# Msi2500.net
KiCad netlist of a schematic drawn in Altium Designer
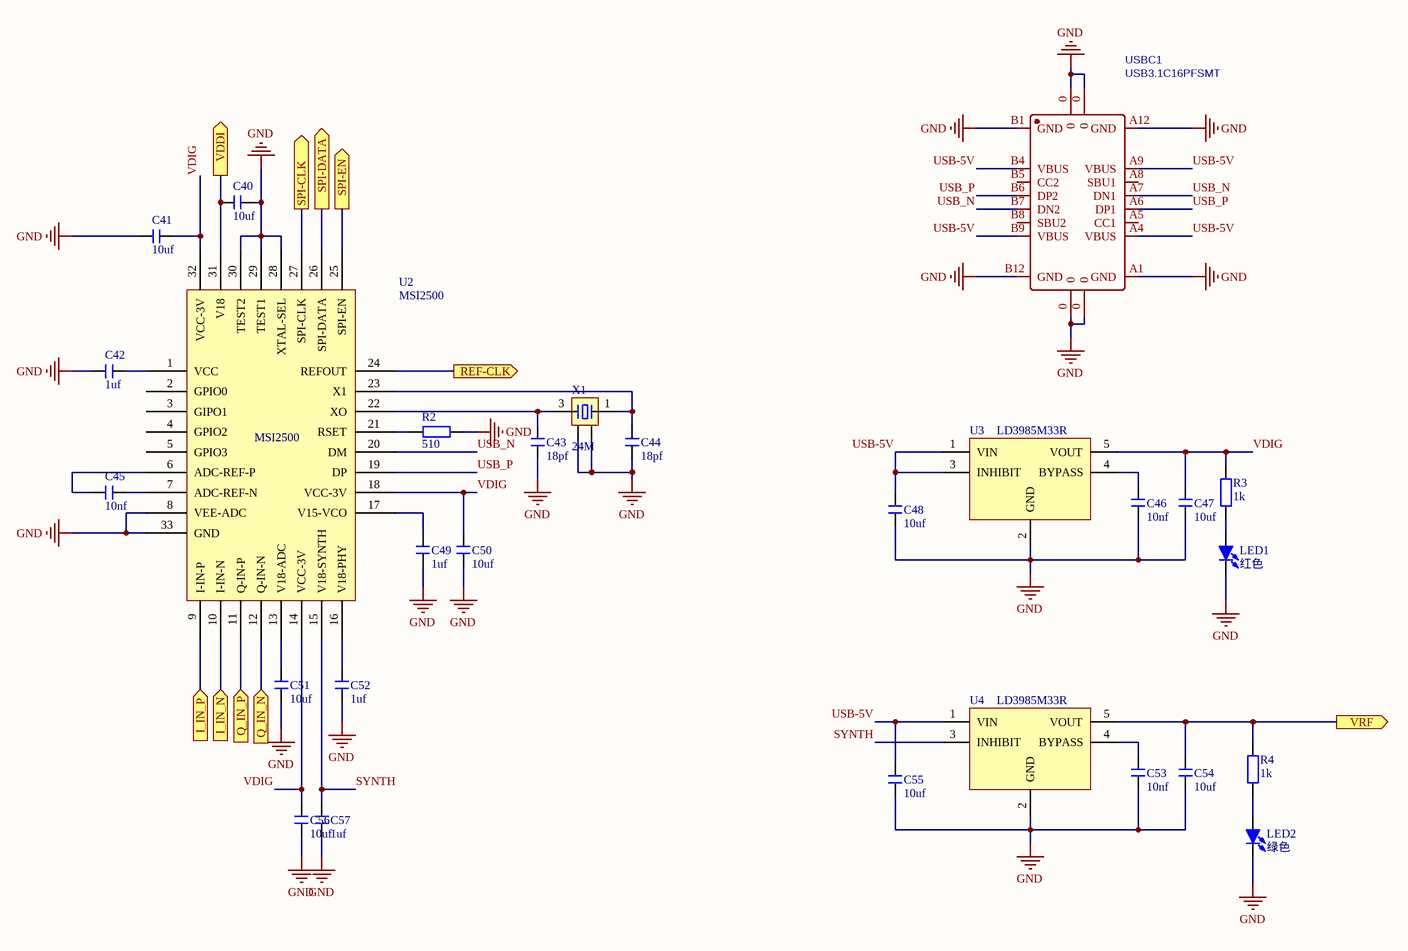
[diagram p0: Msi2500.SchDoc]

(export (version "E")
  (design (tool "Eeschema 10.0.6"))
  (components
    (comp (ref "C40")
      (value "10uf")
      (footprint "C 0603_M")
      (description "无极性贴片电容")
      (fields (field (name "版权归属") "源创客"))
      (libsource (lib "电阻-电容-电感") (part "C"))
    )
    (comp (ref "C41")
      (value "10uf")
      (footprint "C 0603_M")
      (description "无极性贴片电容")
      (fields (field (name "版权归属") "源创客"))
      (libsource (lib "电阻-电容-电感") (part "C"))
    )
    (comp (ref "C42")
      (value "1uf")
      (footprint "C 0603_M")
      (description "无极性贴片电容")
      (fields (field (name "版权归属") "源创客"))
      (libsource (lib "电阻-电容-电感") (part "C"))
    )
    (comp (ref "C43")
      (value "18pf")
      (footprint "C 0603_M")
      (description "无极性贴片电容")
      (fields (field (name "版权归属") "源创客"))
      (libsource (lib "电阻-电容-电感") (part "C"))
    )
    (comp (ref "C44")
      (value "18pf")
      (footprint "C 0603_M")
      (description "无极性贴片电容")
      (fields (field (name "版权归属") "源创客"))
      (libsource (lib "电阻-电容-电感") (part "C"))
    )
    (comp (ref "C45")
      (value "10nf")
      (footprint "C 0603_M")
      (description "无极性贴片电容")
      (fields (field (name "版权归属") "源创客"))
      (libsource (lib "电阻-电容-电感") (part "C"))
    )
    (comp (ref "C46")
      (value "10nf")
      (footprint "C 0603_M")
      (description "无极性贴片电容")
      (fields (field (name "版权归属") "源创客"))
      (libsource (lib "电阻-电容-电感") (part "C"))
    )
    (comp (ref "C47")
      (value "10uf")
      (footprint "C 0603_M")
      (description "无极性贴片电容")
      (fields (field (name "版权归属") "源创客"))
      (libsource (lib "电阻-电容-电感") (part "C"))
    )
    (comp (ref "C48")
      (value "10uf")
      (footprint "C 0603_M")
      (description "无极性贴片电容")
      (fields (field (name "版权归属") "源创客"))
      (libsource (lib "电阻-电容-电感") (part "C"))
    )
    (comp (ref "C49")
      (value "1uf")
      (footprint "C 0603_M")
      (description "无极性贴片电容")
      (fields (field (name "版权归属") "源创客"))
      (libsource (lib "电阻-电容-电感") (part "C"))
    )
    (comp (ref "C50")
      (value "10uf")
      (footprint "C 0603_M")
      (description "无极性贴片电容")
      (fields (field (name "版权归属") "源创客"))
      (libsource (lib "电阻-电容-电感") (part "C"))
    )
    (comp (ref "C51")
      (value "10uf")
      (footprint "C 0603_M")
      (description "无极性贴片电容")
      (fields (field (name "版权归属") "源创客"))
      (libsource (lib "电阻-电容-电感") (part "C"))
    )
    (comp (ref "C52")
      (value "1uf")
      (footprint "C 0603_M")
      (description "无极性贴片电容")
      (fields (field (name "版权归属") "源创客"))
      (libsource (lib "电阻-电容-电感") (part "C"))
    )
    (comp (ref "C53")
      (value "10nf")
      (footprint "C 0603_M")
      (description "无极性贴片电容")
      (fields (field (name "版权归属") "源创客"))
      (libsource (lib "电阻-电容-电感") (part "C"))
    )
    (comp (ref "C54")
      (value "10uf")
      (footprint "C 0603_M")
      (description "无极性贴片电容")
      (fields (field (name "版权归属") "源创客"))
      (libsource (lib "电阻-电容-电感") (part "C"))
    )
    (comp (ref "C55")
      (value "10uf")
      (footprint "C 0603_M")
      (description "无极性贴片电容")
      (fields (field (name "版权归属") "源创客"))
      (libsource (lib "电阻-电容-电感") (part "C"))
    )
    (comp (ref "C56")
      (value "10uf")
      (footprint "C 0603_M")
      (description "无极性贴片电容")
      (fields (field (name "版权归属") "源创客"))
      (libsource (lib "电阻-电容-电感") (part "C"))
    )
    (comp (ref "C57")
      (value "1uf")
      (footprint "C 0603_M")
      (description "无极性贴片电容")
      (fields (field (name "版权归属") "源创客"))
      (libsource (lib "电阻-电容-电感") (part "C"))
    )
    (comp (ref "LED1")
      (value "红色")
      (footprint "LED 0805G")
      (description "贴片LED")
      (fields (field (name "版权归属") "源创客"))
      (libsource (lib "LED") (part "LED-SMD"))
    )
    (comp (ref "LED2")
      (value "绿色")
      (footprint "LED 0805G")
      (description "贴片LED")
      (fields (field (name "版权归属") "源创客"))
      (libsource (lib "LED") (part "LED-SMD"))
    )
    (comp (ref "R2")
      (value "510")
      (footprint "R 0603_M")
      (description "贴片电阻")
      (fields (field (name "版权归属") "源创客"))
      (libsource (lib "电阻-电容-电感") (part "R"))
    )
    (comp (ref "R3")
      (value "1k")
      (footprint "R 0603_M")
      (description "贴片电阻")
      (fields (field (name "版权归属") "源创客"))
      (libsource (lib "电阻-电容-电感") (part "R"))
    )
    (comp (ref "R4")
      (value "1k")
      (footprint "R 0603_M")
      (description "贴片电阻")
      (fields (field (name "版权归属") "源创客"))
      (libsource (lib "电阻-电容-电感") (part "R"))
    )
    (comp (ref "U2") (value "MSI2500") (footprint "QFN32 5x5_M") (libsource (lib "IC芯片") (part "MSI2500")))
    (comp (ref "U3")
      (value "LD3985M33R")
      (footprint "SOT23-5")
      (description "LDO")
      (libsource (lib "IC芯片") (part "LD3985M33R"))
    )
    (comp (ref "U4")
      (value "LD3985M33R")
      (footprint "SOT23-5")
      (description "LDO")
      (libsource (lib "IC芯片") (part "LD3985M33R"))
    )
    (comp (ref "USBC1")
      (value "USB3.1C16PFSMT")
      (footprint "USB-TYPEC-16PIN")
      (fields (field (name "BOM_SUPPLIER PART") "C167321") (field (name "CONTRIBUTOR") "LCSC"))
      (libsource (lib "接口类") (part "USB3.1C16PFSMT"))
    )
    (comp (ref "X1")
      (value "24M")
      (footprint "OSC 3225-4P")
      (description "4脚无源晶振")
      (fields (field (name "版权归属") "源创客"))
      (libsource (lib "保险丝-晶振") (part "XTAL-4P"))
    )
  )
  (nets
    (net (code "1") (name "/I_IN_N") (class "Default")
      (node (ref "U2") (pin "10") (pinfunction "I-IN-N_10") (pintype "passive"))
    )
    (net (code "2") (name "/I_IN_P") (class "Default")
      (node (ref "U2") (pin "9") (pinfunction "I-IN-P_9") (pintype "passive"))
    )
    (net (code "3") (name "/Q_IN_N") (class "Default")
      (node (ref "U2") (pin "12") (pinfunction "Q-IN-N_12") (pintype "passive"))
    )
    (net (code "4") (name "/Q_IN_P") (class "Default")
      (node (ref "U2") (pin "11") (pinfunction "Q-IN-P_11") (pintype "passive"))
    )
    (net (code "5") (name "/REF-CLK") (class "Default")
      (node (ref "U2") (pin "24") (pinfunction "REFOUT_24") (pintype "passive"))
    )
    (net (code "6") (name "/SPI-CLK") (class "Default")
      (node (ref "U2") (pin "27") (pinfunction "SPI-CLK_27") (pintype "passive"))
    )
    (net (code "7") (name "/SPI-DATA") (class "Default")
      (node (ref "U2") (pin "26") (pinfunction "SPI-DATA_26") (pintype "passive"))
    )
    (net (code "8") (name "/SPI-EN") (class "Default")
      (node (ref "U2") (pin "25") (pinfunction "SPI-EN_25") (pintype "passive"))
    )
    (net (code "9") (name "/SYNTH") (class "Default")
      (node (ref "C57") (pin "1") (pinfunction "1_1") (pintype "passive"))
      (node (ref "U2") (pin "15") (pinfunction "V18-SYNTH_15") (pintype "passive"))
      (node (ref "U4") (pin "3") (pinfunction "INHIBIT_3") (pintype "passive"))
    )
    (net (code "10") (name "/USB-5V") (class "Default")
      (node (ref "C48") (pin "2") (pinfunction "2_2") (pintype "passive"))
      (node (ref "C55") (pin "2") (pinfunction "2_2") (pintype "passive"))
      (node (ref "U3") (pin "1") (pinfunction "VIN_1") (pintype "passive"))
      (node (ref "U3") (pin "3") (pinfunction "INHIBIT_3") (pintype "passive"))
      (node (ref "U4") (pin "1") (pinfunction "VIN_1") (pintype "passive"))
      (node (ref "USBC1") (pin "A4") (pinfunction "VBUS_A4") (pintype "passive"))
      (node (ref "USBC1") (pin "A9") (pinfunction "VBUS_A9") (pintype "passive"))
      (node (ref "USBC1") (pin "B4") (pinfunction "VBUS_B4") (pintype "passive"))
      (node (ref "USBC1") (pin "B9") (pinfunction "VBUS_B9") (pintype "passive"))
    )
    (net (code "11") (name "/USB_N") (class "Default")
      (node (ref "U2") (pin "20") (pinfunction "DM_20") (pintype "passive"))
      (node (ref "USBC1") (pin "A7") (pinfunction "DN1_A7") (pintype "passive"))
      (node (ref "USBC1") (pin "B7") (pinfunction "DN2_B7") (pintype "passive"))
    )
    (net (code "12") (name "/USB_P") (class "Default")
      (node (ref "U2") (pin "19") (pinfunction "DP_19") (pintype "passive"))
      (node (ref "USBC1") (pin "A6") (pinfunction "DP1_A6") (pintype "passive"))
      (node (ref "USBC1") (pin "B6") (pinfunction "DP2_B6") (pintype "passive"))
    )
    (net (code "13") (name "/VDDI") (class "Default")
      (node (ref "C40") (pin "2") (pinfunction "2_2") (pintype "passive"))
      (node (ref "U2") (pin "31") (pinfunction "V18_31") (pintype "passive"))
    )
    (net (code "14") (name "/VDIG") (class "Default")
      (node (ref "C41") (pin "1") (pinfunction "1_1") (pintype "passive"))
      (node (ref "C47") (pin "2") (pinfunction "2_2") (pintype "passive"))
      (node (ref "C50") (pin "1") (pinfunction "1_1") (pintype "passive"))
      (node (ref "C56") (pin "1") (pinfunction "1_1") (pintype "passive"))
      (node (ref "R3") (pin "1") (pinfunction "1_1") (pintype "passive"))
      (node (ref "U2") (pin "14") (pinfunction "VCC-3V_14") (pintype "passive"))
      (node (ref "U2") (pin "18") (pinfunction "VCC-3V_18") (pintype "passive"))
      (node (ref "U2") (pin "32") (pinfunction "VCC-3V_32") (pintype "passive"))
      (node (ref "U3") (pin "5") (pinfunction "VOUT_5") (pintype "passive"))
    )
    (net (code "15") (name "/VRF") (class "Default")
      (node (ref "C54") (pin "2") (pinfunction "2_2") (pintype "passive"))
      (node (ref "R4") (pin "1") (pinfunction "1_1") (pintype "passive"))
      (node (ref "U4") (pin "5") (pinfunction "VOUT_5") (pintype "passive"))
    )
    (net (code "16") (name "GND") (class "Default")
      (node (ref "C40") (pin "1") (pinfunction "1_1") (pintype "passive"))
      (node (ref "C41") (pin "2") (pinfunction "2_2") (pintype "passive"))
      (node (ref "C42") (pin "1") (pinfunction "1_1") (pintype "passive"))
      (node (ref "C43") (pin "2") (pinfunction "2_2") (pintype "passive"))
      (node (ref "C44") (pin "2") (pinfunction "2_2") (pintype "passive"))
      (node (ref "C46") (pin "1") (pinfunction "1_1") (pintype "passive"))
      (node (ref "C47") (pin "1") (pinfunction "1_1") (pintype "passive"))
      (node (ref "C48") (pin "1") (pinfunction "1_1") (pintype "passive"))
      (node (ref "C49") (pin "2") (pinfunction "2_2") (pintype "passive"))
      (node (ref "C50") (pin "2") (pinfunction "2_2") (pintype "passive"))
      (node (ref "C51") (pin "2") (pinfunction "2_2") (pintype "passive"))
      (node (ref "C52") (pin "2") (pinfunction "2_2") (pintype "passive"))
      (node (ref "C53") (pin "1") (pinfunction "1_1") (pintype "passive"))
      (node (ref "C54") (pin "1") (pinfunction "1_1") (pintype "passive"))
      (node (ref "C55") (pin "1") (pinfunction "1_1") (pintype "passive"))
      (node (ref "C56") (pin "2") (pinfunction "2_2") (pintype "passive"))
      (node (ref "C57") (pin "2") (pinfunction "2_2") (pintype "passive"))
      (node (ref "LED1") (pin "2") (pinfunction "K_2") (pintype "passive"))
      (node (ref "LED2") (pin "2") (pinfunction "K_2") (pintype "passive"))
      (node (ref "R2") (pin "1") (pinfunction "1_1") (pintype "passive"))
      (node (ref "U2") (pin "28") (pinfunction "XTAL-SEL_28") (pintype "passive"))
      (node (ref "U2") (pin "29") (pinfunction "TEST1_29") (pintype "passive"))
      (node (ref "U2") (pin "30") (pinfunction "TEST2_30") (pintype "passive"))
      (node (ref "U2") (pin "33") (pinfunction "GND_33") (pintype "passive"))
      (node (ref "U2") (pin "8") (pinfunction "VEE-ADC_8") (pintype "passive"))
      (node (ref "U3") (pin "2") (pinfunction "GND_2") (pintype "passive"))
      (node (ref "U4") (pin "2") (pinfunction "GND_2") (pintype "passive"))
      (node (ref "USBC1") (pin "0") (pinfunction "0_0") (pintype "passive"))
      (node (ref "USBC1") (pin "A1") (pinfunction "GND_A1") (pintype "passive"))
      (node (ref "USBC1") (pin "A12") (pinfunction "GND_A12") (pintype "passive"))
      (node (ref "USBC1") (pin "B1") (pinfunction "GND_B1") (pintype "passive"))
      (node (ref "USBC1") (pin "B12") (pinfunction "GND_B12") (pintype "passive"))
      (node (ref "X1") (pin "2") (pinfunction "2_2") (pintype "passive"))
      (node (ref "X1") (pin "4") (pinfunction "4_4") (pintype "passive"))
    )
    (net (code "17") (name "Net-(LED1-A)") (class "Default")
      (node (ref "LED1") (pin "1") (pinfunction "A_1") (pintype "passive"))
      (node (ref "R3") (pin "2") (pinfunction "2_2") (pintype "passive"))
    )
    (net (code "18") (name "Net-(LED2-A)") (class "Default")
      (node (ref "LED2") (pin "1") (pinfunction "A_1") (pintype "passive"))
      (node (ref "R4") (pin "2") (pinfunction "2_2") (pintype "passive"))
    )
    (net (code "19") (name "Net-(U2-ADC-REF-N)") (class "Default")
      (node (ref "C45") (pin "2") (pinfunction "2_2") (pintype "passive"))
      (node (ref "U2") (pin "7") (pinfunction "ADC-REF-N_7") (pintype "passive"))
    )
    (net (code "20") (name "Net-(U2-ADC-REF-P)") (class "Default")
      (node (ref "C45") (pin "1") (pinfunction "1_1") (pintype "passive"))
      (node (ref "U2") (pin "6") (pinfunction "ADC-REF-P_6") (pintype "passive"))
    )
    (net (code "21") (name "Net-(U2-RSET)") (class "Default")
      (node (ref "R2") (pin "2") (pinfunction "2_2") (pintype "passive"))
      (node (ref "U2") (pin "21") (pinfunction "RSET_21") (pintype "passive"))
    )
    (net (code "22") (name "Net-(U2-V15-VCO)") (class "Default")
      (node (ref "C49") (pin "1") (pinfunction "1_1") (pintype "passive"))
      (node (ref "U2") (pin "17") (pinfunction "V15-VCO_17") (pintype "passive"))
    )
    (net (code "23") (name "Net-(U2-V18-ADC)") (class "Default")
      (node (ref "C51") (pin "1") (pinfunction "1_1") (pintype "passive"))
      (node (ref "U2") (pin "13") (pinfunction "V18-ADC_13") (pintype "passive"))
    )
    (net (code "24") (name "Net-(U2-V18-PHY)") (class "Default")
      (node (ref "C52") (pin "1") (pinfunction "1_1") (pintype "passive"))
      (node (ref "U2") (pin "16") (pinfunction "V18-PHY_16") (pintype "passive"))
    )
    (net (code "25") (name "Net-(U2-VCC)") (class "Default")
      (node (ref "C42") (pin "2") (pinfunction "2_2") (pintype "passive"))
      (node (ref "U2") (pin "1") (pinfunction "VCC_1") (pintype "passive"))
    )
    (net (code "26") (name "Net-(U2-X1)") (class "Default")
      (node (ref "C44") (pin "1") (pinfunction "1_1") (pintype "passive"))
      (node (ref "U2") (pin "23") (pinfunction "X1_23") (pintype "passive"))
      (node (ref "X1") (pin "1") (pinfunction "1_1") (pintype "passive"))
    )
    (net (code "27") (name "Net-(U2-XO)") (class "Default")
      (node (ref "C43") (pin "1") (pinfunction "1_1") (pintype "passive"))
      (node (ref "U2") (pin "22") (pinfunction "XO_22") (pintype "passive"))
      (node (ref "X1") (pin "3") (pinfunction "3_3") (pintype "passive"))
    )
    (net (code "28") (name "Net-(U3-BYPASS)") (class "Default")
      (node (ref "C46") (pin "2") (pinfunction "2_2") (pintype "passive"))
      (node (ref "U3") (pin "4") (pinfunction "BYPASS_4") (pintype "passive"))
    )
    (net (code "29") (name "Net-(U4-BYPASS)") (class "Default")
      (node (ref "C53") (pin "2") (pinfunction "2_2") (pintype "passive"))
      (node (ref "U4") (pin "4") (pinfunction "BYPASS_4") (pintype "passive"))
    )
    (net (code "30") (name "unconnected-(U2-GIPO1-Pad3)") (class "Default")
      (node (ref "U2") (pin "3") (pinfunction "GIPO1_3") (pintype "passive"))
    )
    (net (code "31") (name "unconnected-(U2-GPIO0-Pad2)") (class "Default")
      (node (ref "U2") (pin "2") (pinfunction "GPIO0_2") (pintype "passive"))
    )
    (net (code "32") (name "unconnected-(U2-GPIO2-Pad4)") (class "Default")
      (node (ref "U2") (pin "4") (pinfunction "GPIO2_4") (pintype "passive"))
    )
    (net (code "33") (name "unconnected-(U2-GPIO3-Pad5)") (class "Default")
      (node (ref "U2") (pin "5") (pinfunction "GPIO3_5") (pintype "passive"))
    )
    (net (code "34") (name "unconnected-(USBC1-CC1-PadA5)") (class "Default")
      (node (ref "USBC1") (pin "A5") (pinfunction "CC1_A5") (pintype "passive"))
    )
    (net (code "35") (name "unconnected-(USBC1-CC2-PadB5)") (class "Default")
      (node (ref "USBC1") (pin "B5") (pinfunction "CC2_B5") (pintype "passive"))
    )
    (net (code "36") (name "unconnected-(USBC1-SBU1-PadA8)") (class "Default")
      (node (ref "USBC1") (pin "A8") (pinfunction "SBU1_A8") (pintype "passive"))
    )
    (net (code "37") (name "unconnected-(USBC1-SBU2-PadB8)") (class "Default")
      (node (ref "USBC1") (pin "B8") (pinfunction "SBU2_B8") (pintype "passive"))
    )
  )
)
